# TUSB8041_Connectors_2.net
KiCad netlist of a schematic drawn in Altium Designer
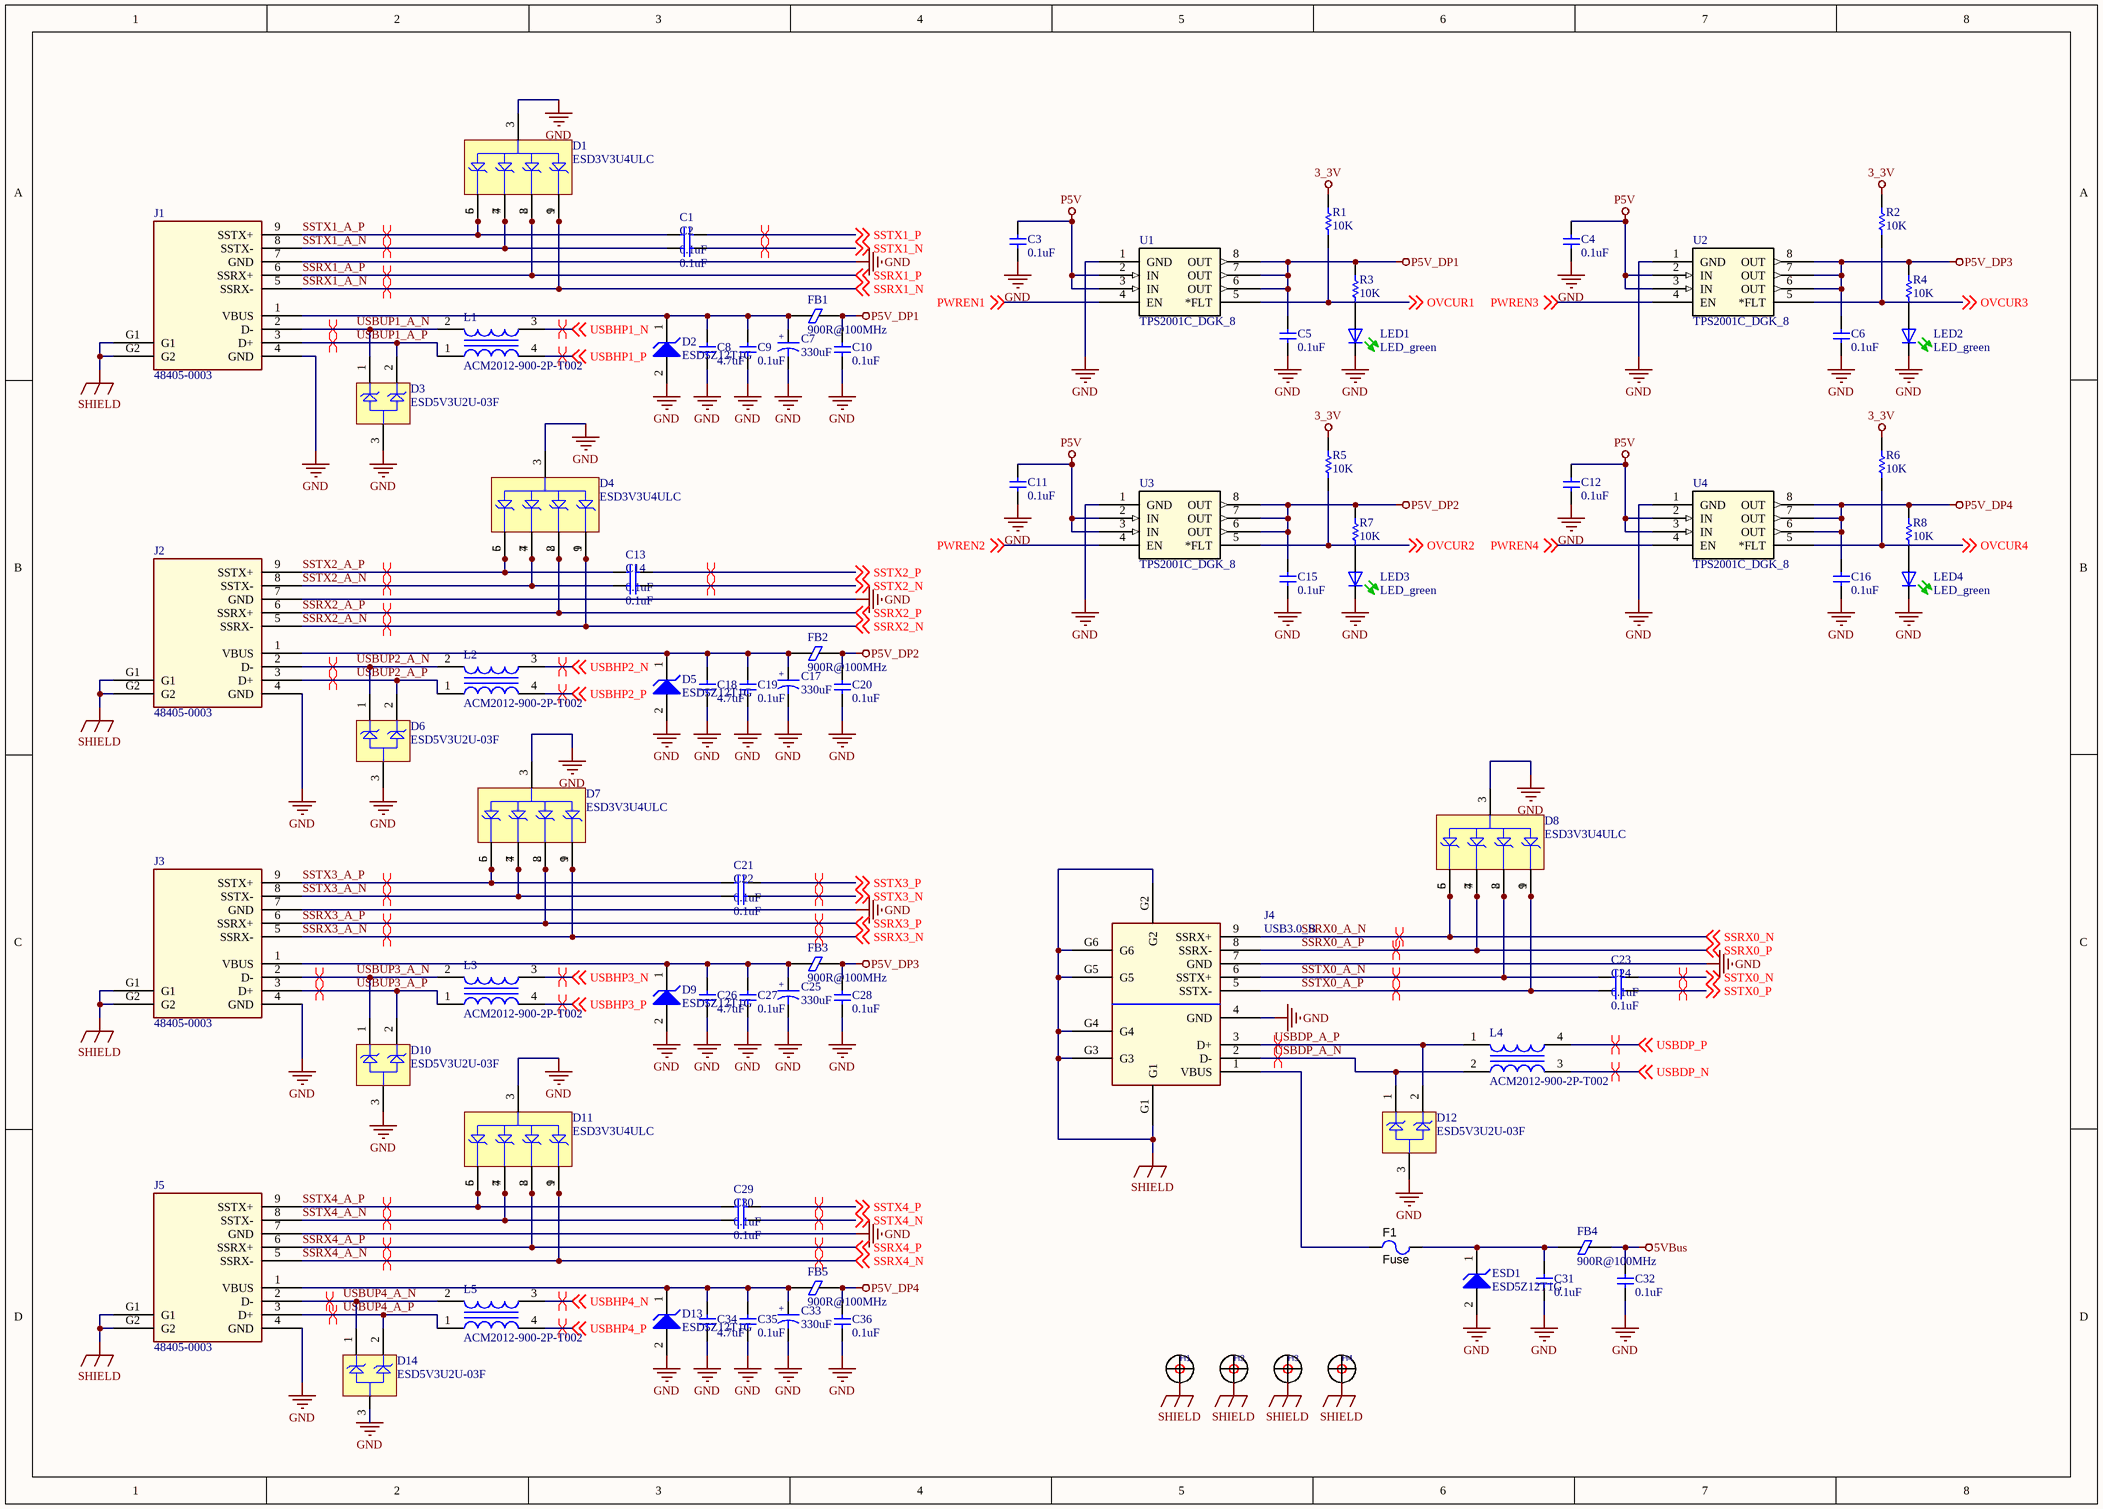
[diagram p0: TUSB8041_Connectors_2.SchDoc]

(export (version "E")
  (design (tool "Eeschema 10.0.6"))
  (components
    (comp (ref "C1")
      (value "0.1uF")
      (footprint "CAP0402")
      (description "Capacitor")
      (fields (field (name "PUBLISHER") "Altium Limited"))
      (libsource (lib "TUSB8041_USB_3.0_Hub") (part "CAP"))
    )
    (comp (ref "C2")
      (value "0.1uF")
      (footprint "CAP0402")
      (description "Capacitor")
      (fields (field (name "PUBLISHER") "Altium Limited"))
      (libsource (lib "TUSB8041_USB_3.0_Hub") (part "CAP"))
    )
    (comp (ref "C3")
      (value "0.1uF")
      (footprint "CAP0603")
      (description "Capacitor")
      (fields (field (name "PUBLISHER") "Altium Limited"))
      (libsource (lib "TUSB8041_USB_3.0_Hub") (part "CAP"))
    )
    (comp (ref "C4")
      (value "0.1uF")
      (footprint "CAP0603")
      (description "Capacitor")
      (fields (field (name "PUBLISHER") "Altium Limited"))
      (libsource (lib "TUSB8041_USB_3.0_Hub") (part "CAP"))
    )
    (comp (ref "C5")
      (value "0.1uF")
      (footprint "CAP0603")
      (description "Capacitor")
      (fields (field (name "PUBLISHER") "Altium Limited"))
      (libsource (lib "TUSB8041_USB_3.0_Hub") (part "CAP"))
    )
    (comp (ref "C6")
      (value "0.1uF")
      (footprint "CAP0603")
      (description "Capacitor")
      (fields (field (name "PUBLISHER") "Altium Limited"))
      (libsource (lib "TUSB8041_USB_3.0_Hub") (part "CAP"))
    )
    (comp (ref "C7")
      (value "330uF")
      (footprint "CAP7343_TANT")
      (libsource (lib "TUSB8041_USB_3.0_Hub") (part "CAP_POL"))
    )
    (comp (ref "C8")
      (value "4.7uF")
      (footprint "CAP0603")
      (description "Capacitor")
      (fields (field (name "PUBLISHER") "Altium Limited"))
      (libsource (lib "TUSB8041_USB_3.0_Hub") (part "CAP"))
    )
    (comp (ref "C9")
      (value "0.1uF")
      (footprint "CAP0603")
      (description "Capacitor")
      (fields (field (name "PUBLISHER") "Altium Limited"))
      (libsource (lib "TUSB8041_USB_3.0_Hub") (part "CAP"))
    )
    (comp (ref "C10")
      (value "0.1uF")
      (footprint "CAP0603")
      (description "Capacitor")
      (fields (field (name "PUBLISHER") "Altium Limited"))
      (libsource (lib "TUSB8041_USB_3.0_Hub") (part "CAP"))
    )
    (comp (ref "C11")
      (value "0.1uF")
      (footprint "CAP0603")
      (description "Capacitor")
      (fields (field (name "PUBLISHER") "Altium Limited"))
      (libsource (lib "TUSB8041_USB_3.0_Hub") (part "CAP"))
    )
    (comp (ref "C12")
      (value "0.1uF")
      (footprint "CAP0603")
      (description "Capacitor")
      (fields (field (name "PUBLISHER") "Altium Limited"))
      (libsource (lib "TUSB8041_USB_3.0_Hub") (part "CAP"))
    )
    (comp (ref "C13")
      (value "0.1uF")
      (footprint "CAP0402")
      (description "Capacitor")
      (fields (field (name "PUBLISHER") "Altium Limited"))
      (libsource (lib "TUSB8041_USB_3.0_Hub") (part "CAP"))
    )
    (comp (ref "C14")
      (value "0.1uF")
      (footprint "CAP0402")
      (description "Capacitor")
      (fields (field (name "PUBLISHER") "Altium Limited"))
      (libsource (lib "TUSB8041_USB_3.0_Hub") (part "CAP"))
    )
    (comp (ref "C15")
      (value "0.1uF")
      (footprint "CAP0603")
      (description "Capacitor")
      (fields (field (name "PUBLISHER") "Altium Limited"))
      (libsource (lib "TUSB8041_USB_3.0_Hub") (part "CAP"))
    )
    (comp (ref "C16")
      (value "0.1uF")
      (footprint "CAP0603")
      (description "Capacitor")
      (fields (field (name "PUBLISHER") "Altium Limited"))
      (libsource (lib "TUSB8041_USB_3.0_Hub") (part "CAP"))
    )
    (comp (ref "C17")
      (value "330uF")
      (footprint "CAP7343_TANT")
      (libsource (lib "TUSB8041_USB_3.0_Hub") (part "CAP_POL"))
    )
    (comp (ref "C18")
      (value "4.7uF")
      (footprint "CAP0603")
      (description "Capacitor")
      (fields (field (name "PUBLISHER") "Altium Limited"))
      (libsource (lib "TUSB8041_USB_3.0_Hub") (part "CAP"))
    )
    (comp (ref "C19")
      (value "0.1uF")
      (footprint "CAP0603")
      (description "Capacitor")
      (fields (field (name "PUBLISHER") "Altium Limited"))
      (libsource (lib "TUSB8041_USB_3.0_Hub") (part "CAP"))
    )
    (comp (ref "C20")
      (value "0.1uF")
      (footprint "CAP0603")
      (description "Capacitor")
      (fields (field (name "PUBLISHER") "Altium Limited"))
      (libsource (lib "TUSB8041_USB_3.0_Hub") (part "CAP"))
    )
    (comp (ref "C21")
      (value "0.1uF")
      (footprint "CAP0402")
      (description "Capacitor")
      (fields (field (name "PUBLISHER") "Altium Limited"))
      (libsource (lib "TUSB8041_USB_3.0_Hub") (part "CAP"))
    )
    (comp (ref "C22")
      (value "0.1uF")
      (footprint "CAP0402")
      (description "Capacitor")
      (fields (field (name "PUBLISHER") "Altium Limited"))
      (libsource (lib "TUSB8041_USB_3.0_Hub") (part "CAP"))
    )
    (comp (ref "C23")
      (value "0.1uF")
      (footprint "CAP0402")
      (description "Capacitor")
      (fields (field (name "PUBLISHER") "Altium Limited"))
      (libsource (lib "TUSB8041_USB_3.0_Hub") (part "CAP"))
    )
    (comp (ref "C24")
      (value "0.1uF")
      (footprint "CAP0402")
      (description "Capacitor")
      (fields (field (name "PUBLISHER") "Altium Limited"))
      (libsource (lib "TUSB8041_USB_3.0_Hub") (part "CAP"))
    )
    (comp (ref "C25")
      (value "330uF")
      (footprint "CAP7343_TANT")
      (libsource (lib "TUSB8041_USB_3.0_Hub") (part "CAP_POL"))
    )
    (comp (ref "C26")
      (value "4.7uF")
      (footprint "CAP0603")
      (description "Capacitor")
      (fields (field (name "PUBLISHER") "Altium Limited"))
      (libsource (lib "TUSB8041_USB_3.0_Hub") (part "CAP"))
    )
    (comp (ref "C27")
      (value "0.1uF")
      (footprint "CAP0603")
      (description "Capacitor")
      (fields (field (name "PUBLISHER") "Altium Limited"))
      (libsource (lib "TUSB8041_USB_3.0_Hub") (part "CAP"))
    )
    (comp (ref "C28")
      (value "0.1uF")
      (footprint "CAP0603")
      (description "Capacitor")
      (fields (field (name "PUBLISHER") "Altium Limited"))
      (libsource (lib "TUSB8041_USB_3.0_Hub") (part "CAP"))
    )
    (comp (ref "C29")
      (value "0.1uF")
      (footprint "CAP0402")
      (description "Capacitor")
      (fields (field (name "PUBLISHER") "Altium Limited"))
      (libsource (lib "TUSB8041_USB_3.0_Hub") (part "CAP"))
    )
    (comp (ref "C30")
      (value "0.1uF")
      (footprint "CAP0402")
      (description "Capacitor")
      (fields (field (name "PUBLISHER") "Altium Limited"))
      (libsource (lib "TUSB8041_USB_3.0_Hub") (part "CAP"))
    )
    (comp (ref "C31")
      (value "0.1uF")
      (footprint "CAP0603")
      (description "Capacitor")
      (fields (field (name "PUBLISHER") "Altium Limited"))
      (libsource (lib "TUSB8041_USB_3.0_Hub") (part "CAP"))
    )
    (comp (ref "C32")
      (value "0.1uF")
      (footprint "CAP0603")
      (description "Capacitor")
      (fields (field (name "PUBLISHER") "Altium Limited"))
      (libsource (lib "TUSB8041_USB_3.0_Hub") (part "CAP"))
    )
    (comp (ref "C33")
      (value "330uF")
      (footprint "CAP7343_TANT")
      (libsource (lib "TUSB8041_USB_3.0_Hub") (part "CAP_POL"))
    )
    (comp (ref "C34")
      (value "4.7uF")
      (footprint "CAP0603")
      (description "Capacitor")
      (fields (field (name "PUBLISHER") "Altium Limited"))
      (libsource (lib "TUSB8041_USB_3.0_Hub") (part "CAP"))
    )
    (comp (ref "C35")
      (value "0.1uF")
      (footprint "CAP0603")
      (description "Capacitor")
      (fields (field (name "PUBLISHER") "Altium Limited"))
      (libsource (lib "TUSB8041_USB_3.0_Hub") (part "CAP"))
    )
    (comp (ref "C36")
      (value "0.1uF")
      (footprint "CAP0603")
      (description "Capacitor")
      (fields (field (name "PUBLISHER") "Altium Limited"))
      (libsource (lib "TUSB8041_USB_3.0_Hub") (part "CAP"))
    )
    (comp (ref "D1")
      (value "ESD3V3U4ULC")
      (footprint "PG-TSLP-9-1")
      (description "Ultra-Low Capacitance ESD / Transient Protection Array, -40 to 125 degC, PG-TSLP-9-1, Reel, Green")
      (fields (field (name "MANUFACTURER") "Infineon"))
      (libsource (lib "小车") (part "ESD3V3U4ULC"))
    )
    (comp (ref "D2")
      (value "ESD5Z12T1G")
      (footprint "ONSC-SOD-523-2-502-01_V")
      (fields (field (name "MANUFACTURER") "On Semiconductor"))
      (libsource (lib "Altium Content Vault") (part "ONSC-K1A2-2"))
    )
    (comp (ref "D3")
      (value "ESD5V3U2U-03F")
      (footprint "INF-PG-TSFP-3-1_V")
      (description "Ultra-Low Capacitance ESD Diode Array, -40 to 125 degC, PG-TSFP-3-1, Reel, Green")
      (fields (field (name "MANUFACTURER") "Infineon"))
      (libsource (lib "Altium Content Vault") (part "INF-D_K1K2A3-3-A"))
    )
    (comp (ref "D4")
      (value "ESD3V3U4ULC")
      (footprint "PG-TSLP-9-1")
      (description "Ultra-Low Capacitance ESD / Transient Protection Array, -40 to 125 degC, PG-TSLP-9-1, Reel, Green")
      (fields (field (name "MANUFACTURER") "Infineon"))
      (libsource (lib "小车") (part "ESD3V3U4ULC"))
    )
    (comp (ref "D5")
      (value "ESD5Z12T1G")
      (footprint "ONSC-SOD-523-2-502-01_V")
      (fields (field (name "MANUFACTURER") "On Semiconductor"))
      (libsource (lib "Altium Content Vault") (part "ONSC-K1A2-2"))
    )
    (comp (ref "D6")
      (value "ESD5V3U2U-03F")
      (footprint "INF-PG-TSFP-3-1_V")
      (description "Ultra-Low Capacitance ESD Diode Array, -40 to 125 degC, PG-TSFP-3-1, Reel, Green")
      (fields (field (name "MANUFACTURER") "Infineon"))
      (libsource (lib "Altium Content Vault") (part "INF-D_K1K2A3-3-A"))
    )
    (comp (ref "D7")
      (value "ESD3V3U4ULC")
      (footprint "PG-TSLP-9-1")
      (description "Ultra-Low Capacitance ESD / Transient Protection Array, -40 to 125 degC, PG-TSLP-9-1, Reel, Green")
      (fields (field (name "MANUFACTURER") "Infineon"))
      (libsource (lib "小车") (part "ESD3V3U4ULC"))
    )
    (comp (ref "D8")
      (value "ESD3V3U4ULC")
      (footprint "PG-TSLP-9-1")
      (description "Ultra-Low Capacitance ESD / Transient Protection Array, -40 to 125 degC, PG-TSLP-9-1, Reel, Green")
      (fields (field (name "MANUFACTURER") "Infineon"))
      (libsource (lib "小车") (part "ESD3V3U4ULC"))
    )
    (comp (ref "D9")
      (value "ESD5Z12T1G")
      (footprint "ONSC-SOD-523-2-502-01_V")
      (fields (field (name "MANUFACTURER") "On Semiconductor"))
      (libsource (lib "Altium Content Vault") (part "ONSC-K1A2-2"))
    )
    (comp (ref "D10")
      (value "ESD5V3U2U-03F")
      (footprint "INF-PG-TSFP-3-1_V")
      (description "Ultra-Low Capacitance ESD Diode Array, -40 to 125 degC, PG-TSFP-3-1, Reel, Green")
      (fields (field (name "MANUFACTURER") "Infineon"))
      (libsource (lib "Altium Content Vault") (part "INF-D_K1K2A3-3-A"))
    )
    (comp (ref "D11")
      (value "ESD3V3U4ULC")
      (footprint "PG-TSLP-9-1")
      (description "Ultra-Low Capacitance ESD / Transient Protection Array, -40 to 125 degC, PG-TSLP-9-1, Reel, Green")
      (fields (field (name "MANUFACTURER") "Infineon"))
      (libsource (lib "小车") (part "ESD3V3U4ULC"))
    )
    (comp (ref "D12")
      (value "ESD5V3U2U-03F")
      (footprint "INF-PG-TSFP-3-1_V")
      (description "Ultra-Low Capacitance ESD Diode Array, -40 to 125 degC, PG-TSFP-3-1, Reel, Green")
      (fields (field (name "MANUFACTURER") "Infineon"))
      (libsource (lib "Altium Content Vault") (part "INF-D_K1K2A3-3-A"))
    )
    (comp (ref "D13")
      (value "ESD5Z12T1G")
      (footprint "ONSC-SOD-523-2-502-01_V")
      (fields (field (name "MANUFACTURER") "On Semiconductor"))
      (libsource (lib "Altium Content Vault") (part "ONSC-K1A2-2"))
    )
    (comp (ref "D14")
      (value "ESD5V3U2U-03F")
      (footprint "INF-PG-TSFP-3-1_V")
      (description "Ultra-Low Capacitance ESD Diode Array, -40 to 125 degC, PG-TSFP-3-1, Reel, Green")
      (fields (field (name "MANUFACTURER") "Infineon"))
      (libsource (lib "Altium Content Vault") (part "INF-D_K1K2A3-3-A"))
    )
    (comp (ref "ESD1")
      (value "ESD5Z12T1G")
      (footprint "ONSC-SOD-523-2-502-01_V")
      (fields (field (name "MANUFACTURER") "On Semiconductor"))
      (libsource (lib "Altium Content Vault") (part "ONSC-K1A2-2"))
    )
    (comp (ref "F1")
      (value "Fuse")
      (footprint "FUSE1206")
      (fields
        (field (name "PARTNUMBER") "NANOSMDC020F-2")
        (field (name "MANUFACTURER") "TE Connectivity")
        (field (name "PUBLISHER") "Texas Instruments")
        (field (name "SYMBOLCREATOR") "a0412235")
      )
      (libsource (lib "TUSB8041_USB_3.0_Hub") (part "Fuse"))
    )
    (comp (ref "FB1")
      (value "900R@100MHz")
      (footprint "L0805")
      (libsource (lib "TUSB8041_USB_3.0_Hub") (part "Ferrite Bead"))
    )
    (comp (ref "FB2")
      (value "900R@100MHz")
      (footprint "L0805")
      (libsource (lib "TUSB8041_USB_3.0_Hub") (part "Ferrite Bead"))
    )
    (comp (ref "FB3")
      (value "900R@100MHz")
      (footprint "L0805")
      (libsource (lib "TUSB8041_USB_3.0_Hub") (part "Ferrite Bead"))
    )
    (comp (ref "FB4")
      (value "900R@100MHz")
      (footprint "L0805")
      (libsource (lib "TUSB8041_USB_3.0_Hub") (part "Ferrite Bead"))
    )
    (comp (ref "FB5")
      (value "900R@100MHz")
      (footprint "L0805")
      (libsource (lib "TUSB8041_USB_3.0_Hub") (part "Ferrite Bead"))
    )
    (comp (ref "H1")
      (value "HOLE")
      (footprint "HOLE_Φ3_1_2D")
      (libsource (lib "TUSB8041_USB_3.0_Hub") (part "HOLE"))
    )
    (comp (ref "H2")
      (value "HOLE")
      (footprint "HOLE_Φ3_1_2D")
      (libsource (lib "TUSB8041_USB_3.0_Hub") (part "HOLE"))
    )
    (comp (ref "H3")
      (value "HOLE")
      (footprint "HOLE_Φ3_1_2D")
      (libsource (lib "TUSB8041_USB_3.0_Hub") (part "HOLE"))
    )
    (comp (ref "H4")
      (value "HOLE")
      (footprint "HOLE_Φ3_1_2D")
      (libsource (lib "TUSB8041_USB_3.0_Hub") (part "HOLE"))
    )
    (comp (ref "J1")
      (value "48405-0003")
      (footprint "CN_USB30_A")
      (libsource (lib "TUSB8041_USB_3.0_Hub") (part "USB-UEA11123-4HK1-4H"))
    )
    (comp (ref "J2")
      (value "48405-0003")
      (footprint "CN_USB30_A")
      (libsource (lib "TUSB8041_USB_3.0_Hub") (part "USB-UEA11123-4HK1-4H"))
    )
    (comp (ref "J3")
      (value "48405-0003")
      (footprint "CN_USB30_A")
      (libsource (lib "TUSB8041_USB_3.0_Hub") (part "USB-UEA11123-4HK1-4H"))
    )
    (comp (ref "J4")
      (value "USB3.0_B")
      (footprint "ASS_4224_CO")
      (libsource (lib "TUSB8041_USB_3.0_Hub") (part "USB3.0_B"))
    )
    (comp (ref "J5")
      (value "48405-0003")
      (footprint "CN_USB30_A")
      (libsource (lib "TUSB8041_USB_3.0_Hub") (part "USB-UEA11123-4HK1-4H"))
    )
    (comp (ref "L1")
      (value "ACM2012-900-2P-T002")
      (footprint "TDK-ACM2012_V")
      (description "Common Mode Filter, 90 Ohm, 50 V, -40 to 85 degC, 4-Pin SMD, RoHS, Tape and Reel")
      (fields (field (name "PART NO") "ACM2012-900-2P-T") (field (name "MANUFACTURER") "TDKCorporation"))
      (libsource (lib "Altium Content Vault") (part "IND-CHOKE-4_C"))
    )
    (comp (ref "L2")
      (value "ACM2012-900-2P-T002")
      (footprint "TDK-ACM2012_V")
      (description "Common Mode Filter, 90 Ohm, 50 V, -40 to 85 degC, 4-Pin SMD, RoHS, Tape and Reel")
      (fields (field (name "PART NO") "ACM2012-900-2P-T") (field (name "MANUFACTURER") "TDKCorporation"))
      (libsource (lib "Altium Content Vault") (part "IND-CHOKE-4_C"))
    )
    (comp (ref "L3")
      (value "ACM2012-900-2P-T002")
      (footprint "TDK-ACM2012_V")
      (description "Common Mode Filter, 90 Ohm, 50 V, -40 to 85 degC, 4-Pin SMD, RoHS, Tape and Reel")
      (fields (field (name "PART NO") "ACM2012-900-2P-T") (field (name "MANUFACTURER") "TDKCorporation"))
      (libsource (lib "Altium Content Vault") (part "IND-CHOKE-4_C"))
    )
    (comp (ref "L4")
      (value "ACM2012-900-2P-T002")
      (footprint "TDK-ACM2012_V")
      (description "Common Mode Filter, 90 Ohm, 50 V, -40 to 85 degC, 4-Pin SMD, RoHS, Tape and Reel")
      (fields (field (name "PART NO") "ACM2012-900-2P-T") (field (name "MANUFACTURER") "TDKCorporation"))
      (libsource (lib "") (part "IND-CHOKE-4_C_1"))
    )
    (comp (ref "L5")
      (value "ACM2012-900-2P-T002")
      (footprint "TDK-ACM2012_V")
      (description "Common Mode Filter, 90 Ohm, 50 V, -40 to 85 degC, 4-Pin SMD, RoHS, Tape and Reel")
      (fields (field (name "PART NO") "ACM2012-900-2P-T") (field (name "MANUFACTURER") "TDKCorporation"))
      (libsource (lib "Altium Content Vault") (part "IND-CHOKE-4_C"))
    )
    (comp (ref "LED1")
      (value "LED_green")
      (footprint "LED-0603-GREEN")
      (libsource (lib "TUSB8041_USB_3.0_Hub") (part "LED_green"))
    )
    (comp (ref "LED2")
      (value "LED_green")
      (footprint "LED-0603-GREEN")
      (libsource (lib "TUSB8041_USB_3.0_Hub") (part "LED_green"))
    )
    (comp (ref "LED3")
      (value "LED_green")
      (footprint "LED-0603-GREEN")
      (libsource (lib "TUSB8041_USB_3.0_Hub") (part "LED_green"))
    )
    (comp (ref "LED4")
      (value "LED_green")
      (footprint "LED-0603-GREEN")
      (libsource (lib "TUSB8041_USB_3.0_Hub") (part "LED_green"))
    )
    (comp (ref "R1")
      (value "10K")
      (footprint "RES0603")
      (description "Resistor")
      (fields (field (name "PUBLISHER") "Altium Limited"))
      (libsource (lib "TUSB8041_USB_3.0_Hub") (part "RES"))
    )
    (comp (ref "R2")
      (value "10K")
      (footprint "RES0603")
      (description "Resistor")
      (fields (field (name "PUBLISHER") "Altium Limited"))
      (libsource (lib "TUSB8041_USB_3.0_Hub") (part "RES"))
    )
    (comp (ref "R3")
      (value "10K")
      (footprint "RES0603")
      (description "Resistor")
      (fields (field (name "PUBLISHER") "Altium Limited"))
      (libsource (lib "TUSB8041_USB_3.0_Hub") (part "RES"))
    )
    (comp (ref "R4")
      (value "10K")
      (footprint "RES0603")
      (description "Resistor")
      (fields (field (name "PUBLISHER") "Altium Limited"))
      (libsource (lib "TUSB8041_USB_3.0_Hub") (part "RES"))
    )
    (comp (ref "R5")
      (value "10K")
      (footprint "RES0603")
      (description "Resistor")
      (fields (field (name "PUBLISHER") "Altium Limited"))
      (libsource (lib "TUSB8041_USB_3.0_Hub") (part "RES"))
    )
    (comp (ref "R6")
      (value "10K")
      (footprint "RES0603")
      (description "Resistor")
      (fields (field (name "PUBLISHER") "Altium Limited"))
      (libsource (lib "TUSB8041_USB_3.0_Hub") (part "RES"))
    )
    (comp (ref "R7")
      (value "10K")
      (footprint "RES0603")
      (description "Resistor")
      (fields (field (name "PUBLISHER") "Altium Limited"))
      (libsource (lib "TUSB8041_USB_3.0_Hub") (part "RES"))
    )
    (comp (ref "R8")
      (value "10K")
      (footprint "RES0603")
      (description "Resistor")
      (fields (field (name "PUBLISHER") "Altium Limited"))
      (libsource (lib "TUSB8041_USB_3.0_Hub") (part "RES"))
    )
    (comp (ref "U1")
      (value "TPS2001C_DGK_8")
      (footprint "VSSOP8")
      (description "2A_MOS_PSW")
      (fields
        (field (name "MANUFACTURER_PART_NUMBER") "tps2001c_dgk_8")
        (field (name "GENERIC_PART_NUMBER") "TPS2001C")
      )
      (libsource (lib "TUSB8041_USB_3.0_Hub") (part "TPS2001C_DGK_8"))
    )
    (comp (ref "U2")
      (value "TPS2001C_DGK_8")
      (footprint "VSSOP8")
      (description "2A_MOS_PSW")
      (fields
        (field (name "MANUFACTURER_PART_NUMBER") "tps2001c_dgk_8")
        (field (name "GENERIC_PART_NUMBER") "TPS2001C")
      )
      (libsource (lib "TUSB8041_USB_3.0_Hub") (part "TPS2001C_DGK_8"))
    )
    (comp (ref "U3")
      (value "TPS2001C_DGK_8")
      (footprint "VSSOP8")
      (description "2A_MOS_PSW")
      (fields
        (field (name "MANUFACTURER_PART_NUMBER") "tps2001c_dgk_8")
        (field (name "GENERIC_PART_NUMBER") "TPS2001C")
      )
      (libsource (lib "TUSB8041_USB_3.0_Hub") (part "TPS2001C_DGK_8"))
    )
    (comp (ref "U4")
      (value "TPS2001C_DGK_8")
      (footprint "VSSOP8")
      (description "2A_MOS_PSW")
      (fields
        (field (name "MANUFACTURER_PART_NUMBER") "tps2001c_dgk_8")
        (field (name "GENERIC_PART_NUMBER") "TPS2001C")
      )
      (libsource (lib "TUSB8041_USB_3.0_Hub") (part "TPS2001C_DGK_8"))
    )
  )
  (nets
    (net (code "1") (name "/SSTX0_A_N") (class "Default")
      (node (ref "C23") (pin "2") (pinfunction "2_2") (pintype "passive"))
      (node (ref "D8") (pin "2") (pinfunction "K2_2") (pintype "passive"))
      (node (ref "D8") (pin "8") (pinfunction "K8_8") (pintype "passive"))
      (node (ref "J4") (pin "6") (pinfunction "SSTX+_6") (pintype "passive"))
    )
    (net (code "2") (name "/SSTX0_A_P") (class "Default")
      (node (ref "C24") (pin "2") (pinfunction "2_2") (pintype "passive"))
      (node (ref "D8") (pin "1") (pinfunction "K1_1") (pintype "passive"))
      (node (ref "D8") (pin "9") (pinfunction "K9_9") (pintype "passive"))
      (node (ref "J4") (pin "5") (pinfunction "SSTX-_5") (pintype "passive"))
    )
    (net (code "3") (name "/SSTX1_A_N") (class "Default")
      (node (ref "C2") (pin "2") (pinfunction "2_2") (pintype "passive"))
      (node (ref "D1") (pin "4") (pinfunction "K4_4") (pintype "passive"))
      (node (ref "D1") (pin "7") (pinfunction "K7_7") (pintype "passive"))
      (node (ref "J1") (pin "8") (pinfunction "SSTX-_8") (pintype "passive"))
    )
    (net (code "4") (name "/SSTX1_A_P") (class "Default")
      (node (ref "C1") (pin "2") (pinfunction "2_2") (pintype "passive"))
      (node (ref "D1") (pin "5") (pinfunction "K5_5") (pintype "passive"))
      (node (ref "D1") (pin "6") (pinfunction "K6_6") (pintype "passive"))
      (node (ref "J1") (pin "9") (pinfunction "SSTX+_9") (pintype "passive"))
    )
    (net (code "5") (name "/SSTX2_A_N") (class "Default")
      (node (ref "C14") (pin "2") (pinfunction "2_2") (pintype "passive"))
      (node (ref "D4") (pin "4") (pinfunction "K4_4") (pintype "passive"))
      (node (ref "D4") (pin "7") (pinfunction "K7_7") (pintype "passive"))
      (node (ref "J2") (pin "8") (pinfunction "SSTX-_8") (pintype "passive"))
    )
    (net (code "6") (name "/SSTX2_A_P") (class "Default")
      (node (ref "C13") (pin "2") (pinfunction "2_2") (pintype "passive"))
      (node (ref "D4") (pin "5") (pinfunction "K5_5") (pintype "passive"))
      (node (ref "D4") (pin "6") (pinfunction "K6_6") (pintype "passive"))
      (node (ref "J2") (pin "9") (pinfunction "SSTX+_9") (pintype "passive"))
    )
    (net (code "7") (name "/SSTX3_A_N") (class "Default")
      (node (ref "C22") (pin "2") (pinfunction "2_2") (pintype "passive"))
      (node (ref "D7") (pin "4") (pinfunction "K4_4") (pintype "passive"))
      (node (ref "D7") (pin "7") (pinfunction "K7_7") (pintype "passive"))
      (node (ref "J3") (pin "8") (pinfunction "SSTX-_8") (pintype "passive"))
    )
    (net (code "8") (name "/SSTX3_A_P") (class "Default")
      (node (ref "C21") (pin "2") (pinfunction "2_2") (pintype "passive"))
      (node (ref "D7") (pin "5") (pinfunction "K5_5") (pintype "passive"))
      (node (ref "D7") (pin "6") (pinfunction "K6_6") (pintype "passive"))
      (node (ref "J3") (pin "9") (pinfunction "SSTX+_9") (pintype "passive"))
    )
    (net (code "9") (name "/SSTX4_A_N") (class "Default")
      (node (ref "C30") (pin "2") (pinfunction "2_2") (pintype "passive"))
      (node (ref "D11") (pin "4") (pinfunction "K4_4") (pintype "passive"))
      (node (ref "D11") (pin "7") (pinfunction "K7_7") (pintype "passive"))
      (node (ref "J5") (pin "8") (pinfunction "SSTX-_8") (pintype "passive"))
    )
    (net (code "10") (name "/SSTX4_A_P") (class "Default")
      (node (ref "C29") (pin "2") (pinfunction "2_2") (pintype "passive"))
      (node (ref "D11") (pin "5") (pinfunction "K5_5") (pintype "passive"))
      (node (ref "D11") (pin "6") (pinfunction "K6_6") (pintype "passive"))
      (node (ref "J5") (pin "9") (pinfunction "SSTX+_9") (pintype "passive"))
    )
    (net (code "11") (name "/USBDP_A_N") (class "Default")
      (node (ref "D12") (pin "1") (pinfunction "K1_1") (pintype "passive"))
      (node (ref "J4") (pin "2") (pinfunction "D-_2") (pintype "passive"))
      (node (ref "L4") (pin "2") (pinfunction "2_2") (pintype "passive"))
    )
    (net (code "12") (name "/USBDP_A_P") (class "Default")
      (node (ref "D12") (pin "2") (pinfunction "K2_2") (pintype "passive"))
      (node (ref "J4") (pin "3") (pinfunction "D+_3") (pintype "passive"))
      (node (ref "L4") (pin "1") (pinfunction "1_1") (pintype "passive"))
    )
    (net (code "13") (name "/USBUP1_A_N") (class "Default")
      (node (ref "D3") (pin "1") (pinfunction "K1_1") (pintype "passive"))
      (node (ref "J1") (pin "2") (pinfunction "D-_2") (pintype "passive"))
      (node (ref "L1") (pin "2") (pinfunction "2_2") (pintype "passive"))
    )
    (net (code "14") (name "/USBUP1_A_P") (class "Default")
      (node (ref "D3") (pin "2") (pinfunction "K2_2") (pintype "passive"))
      (node (ref "J1") (pin "3") (pinfunction "D+_3") (pintype "passive"))
      (node (ref "L1") (pin "1") (pinfunction "1_1") (pintype "passive"))
    )
    (net (code "15") (name "/USBUP2_A_N") (class "Default")
      (node (ref "D6") (pin "1") (pinfunction "K1_1") (pintype "passive"))
      (node (ref "J2") (pin "2") (pinfunction "D-_2") (pintype "passive"))
      (node (ref "L2") (pin "2") (pinfunction "2_2") (pintype "passive"))
    )
    (net (code "16") (name "/USBUP2_A_P") (class "Default")
      (node (ref "D6") (pin "2") (pinfunction "K2_2") (pintype "passive"))
      (node (ref "J2") (pin "3") (pinfunction "D+_3") (pintype "passive"))
      (node (ref "L2") (pin "1") (pinfunction "1_1") (pintype "passive"))
    )
    (net (code "17") (name "/USBUP3_A_N") (class "Default")
      (node (ref "D10") (pin "1") (pinfunction "K1_1") (pintype "passive"))
      (node (ref "J3") (pin "2") (pinfunction "D-_2") (pintype "passive"))
      (node (ref "L3") (pin "2") (pinfunction "2_2") (pintype "passive"))
    )
    (net (code "18") (name "/USBUP3_A_P") (class "Default")
      (node (ref "D10") (pin "2") (pinfunction "K2_2") (pintype "passive"))
      (node (ref "J3") (pin "3") (pinfunction "D+_3") (pintype "passive"))
      (node (ref "L3") (pin "1") (pinfunction "1_1") (pintype "passive"))
    )
    (net (code "19") (name "/USBUP4_A_N") (class "Default")
      (node (ref "D14") (pin "1") (pinfunction "K1_1") (pintype "passive"))
      (node (ref "J5") (pin "2") (pinfunction "D-_2") (pintype "passive"))
      (node (ref "L5") (pin "2") (pinfunction "2_2") (pintype "passive"))
    )
    (net (code "20") (name "/USBUP4_A_P") (class "Default")
      (node (ref "D14") (pin "2") (pinfunction "K2_2") (pintype "passive"))
      (node (ref "J5") (pin "3") (pinfunction "D+_3") (pintype "passive"))
      (node (ref "L5") (pin "1") (pinfunction "1_1") (pintype "passive"))
    )
    (net (code "21") (name "3_3V") (class "Default")
      (node (ref "R1") (pin "1") (pinfunction "1_1") (pintype "passive"))
      (node (ref "R2") (pin "1") (pinfunction "1_1") (pintype "passive"))
      (node (ref "R5") (pin "1") (pinfunction "1_1") (pintype "passive"))
      (node (ref "R6") (pin "1") (pinfunction "1_1") (pintype "passive"))
    )
    (net (code "22") (name "5VBus") (class "Default")
      (node (ref "C32") (pin "2") (pinfunction "2_2") (pintype "passive"))
      (node (ref "FB4") (pin "2") (pintype "passive"))
    )
    (net (code "23") (name "GND") (class "Default")
      (node (ref "C10") (pin "1") (pinfunction "1_1") (pintype "passive"))
      (node (ref "C11") (pin "1") (pinfunction "1_1") (pintype "passive"))
      (node (ref "C12") (pin "1") (pinfunction "1_1") (pintype "passive"))
      (node (ref "C15") (pin "1") (pinfunction "1_1") (pintype "passive"))
      (node (ref "C16") (pin "1") (pinfunction "1_1") (pintype "passive"))
      (node (ref "C17") (pin "2") (pinfunction "2_2") (pintype "passive"))
      (node (ref "C18") (pin "1") (pinfunction "1_1") (pintype "passive"))
      (node (ref "C19") (pin "1") (pinfunction "1_1") (pintype "passive"))
      (node (ref "C20") (pin "1") (pinfunction "1_1") (pintype "passive"))
      (node (ref "C25") (pin "2") (pinfunction "2_2") (pintype "passive"))
      (node (ref "C26") (pin "1") (pinfunction "1_1") (pintype "passive"))
      (node (ref "C27") (pin "1") (pinfunction "1_1") (pintype "passive"))
      (node (ref "C28") (pin "1") (pinfunction "1_1") (pintype "passive"))
      (node (ref "C3") (pin "1") (pinfunction "1_1") (pintype "passive"))
      (node (ref "C31") (pin "1") (pinfunction "1_1") (pintype "passive"))
      (node (ref "C32") (pin "1") (pinfunction "1_1") (pintype "passive"))
      (node (ref "C33") (pin "2") (pinfunction "2_2") (pintype "passive"))
      (node (ref "C34") (pin "1") (pinfunction "1_1") (pintype "passive"))
      (node (ref "C35") (pin "1") (pinfunction "1_1") (pintype "passive"))
      (node (ref "C36") (pin "1") (pinfunction "1_1") (pintype "passive"))
      (node (ref "C4") (pin "1") (pinfunction "1_1") (pintype "passive"))
      (node (ref "C5") (pin "1") (pinfunction "1_1") (pintype "passive"))
      (node (ref "C6") (pin "1") (pinfunction "1_1") (pintype "passive"))
      (node (ref "C7") (pin "2") (pinfunction "2_2") (pintype "passive"))
      (node (ref "C8") (pin "1") (pinfunction "1_1") (pintype "passive"))
      (node (ref "C9") (pin "1") (pinfunction "1_1") (pintype "passive"))
      (node (ref "D1") (pin "3") (pinfunction "A_3") (pintype "passive"))
      (node (ref "D10") (pin "3") (pinfunction "A_3") (pintype "passive"))
      (node (ref "D11") (pin "3") (pinfunction "A_3") (pintype "passive"))
      (node (ref "D12") (pin "3") (pinfunction "A_3") (pintype "passive"))
      (node (ref "D13") (pin "2") (pinfunction "A_2") (pintype "passive"))
      (node (ref "D14") (pin "3") (pinfunction "A_3") (pintype "passive"))
      (node (ref "D2") (pin "2") (pinfunction "A_2") (pintype "passive"))
      (node (ref "D3") (pin "3") (pinfunction "A_3") (pintype "passive"))
      (node (ref "D4") (pin "3") (pinfunction "A_3") (pintype "passive"))
      (node (ref "D5") (pin "2") (pinfunction "A_2") (pintype "passive"))
      (node (ref "D6") (pin "3") (pinfunction "A_3") (pintype "passive"))
      (node (ref "D7") (pin "3") (pinfunction "A_3") (pintype "passive"))
      (node (ref "D8") (pin "3") (pinfunction "A_3") (pintype "passive"))
      (node (ref "D9") (pin "2") (pinfunction "A_2") (pintype "passive"))
      (node (ref "ESD1") (pin "2") (pinfunction "A_2") (pintype "passive"))
      (node (ref "J1") (pin "4") (pinfunction "GND_4") (pintype "power_in"))
      (node (ref "J1") (pin "7") (pinfunction "GND_7") (pintype "power_in"))
      (node (ref "J2") (pin "4") (pinfunction "GND_4") (pintype "power_in"))
      (node (ref "J2") (pin "7") (pinfunction "GND_7") (pintype "power_in"))
      (node (ref "J3") (pin "4") (pinfunction "GND_4") (pintype "power_in"))
      (node (ref "J3") (pin "7") (pinfunction "GND_7") (pintype "power_in"))
      (node (ref "J4") (pin "4") (pinfunction "GND_4") (pintype "power_in"))
      (node (ref "J4") (pin "7") (pinfunction "GND_7") (pintype "power_in"))
      (node (ref "J5") (pin "4") (pinfunction "GND_4") (pintype "power_in"))
      (node (ref "J5") (pin "7") (pinfunction "GND_7") (pintype "power_in"))
      (node (ref "LED1") (pin "K") (pinfunction "C_K") (pintype "power_in"))
      (node (ref "LED2") (pin "K") (pinfunction "C_K") (pintype "power_in"))
      (node (ref "LED3") (pin "K") (pinfunction "C_K") (pintype "power_in"))
      (node (ref "LED4") (pin "K") (pinfunction "C_K") (pintype "power_in"))
      (node (ref "U1") (pin "1") (pinfunction "GND_1") (pintype "power_in"))
      (node (ref "U2") (pin "1") (pinfunction "GND_1") (pintype "power_in"))
      (node (ref "U3") (pin "1") (pinfunction "GND_1") (pintype "power_in"))
      (node (ref "U4") (pin "1") (pinfunction "GND_1") (pintype "power_in"))
    )
    (net (code "24") (name "Net-(D2-K)") (class "Default")
      (node (ref "C7") (pin "1") (pinfunction "1_1") (pintype "passive"))
      (node (ref "C8") (pin "2") (pinfunction "2_2") (pintype "passive"))
      (node (ref "C9") (pin "2") (pinfunction "2_2") (pintype "passive"))
      (node (ref "D2") (pin "1") (pinfunction "K_1") (pintype "passive"))
      (node (ref "FB1") (pin "1") (pintype "passive"))
      (node (ref "J1") (pin "1") (pinfunction "VBUS_1") (pintype "passive"))
    )
    (net (code "25") (name "Net-(D5-K)") (class "Default")
      (node (ref "C17") (pin "1") (pinfunction "1_1") (pintype "passive"))
      (node (ref "C18") (pin "2") (pinfunction "2_2") (pintype "passive"))
      (node (ref "C19") (pin "2") (pinfunction "2_2") (pintype "passive"))
      (node (ref "D5") (pin "1") (pinfunction "K_1") (pintype "passive"))
      (node (ref "FB2") (pin "1") (pintype "passive"))
      (node (ref "J2") (pin "1") (pinfunction "VBUS_1") (pintype "passive"))
    )
    (net (code "26") (name "Net-(D9-K)") (class "Default")
      (node (ref "C25") (pin "1") (pinfunction "1_1") (pintype "passive"))
      (node (ref "C26") (pin "2") (pinfunction "2_2") (pintype "passive"))
      (node (ref "C27") (pin "2") (pinfunction "2_2") (pintype "passive"))
      (node (ref "D9") (pin "1") (pinfunction "K_1") (pintype "passive"))
      (node (ref "FB3") (pin "1") (pintype "passive"))
      (node (ref "J3") (pin "1") (pinfunction "VBUS_1") (pintype "passive"))
    )
    (net (code "27") (name "Net-(D13-K)") (class "Default")
      (node (ref "C33") (pin "1") (pinfunction "1_1") (pintype "passive"))
      (node (ref "C34") (pin "2") (pinfunction "2_2") (pintype "passive"))
      (node (ref "C35") (pin "2") (pinfunction "2_2") (pintype "passive"))
      (node (ref "D13") (pin "1") (pinfunction "K_1") (pintype "passive"))
      (node (ref "FB5") (pin "1") (pintype "passive"))
      (node (ref "J5") (pin "1") (pinfunction "VBUS_1") (pintype "passive"))
    )
    (net (code "28") (name "Net-(ESD1-K)") (class "Default")
      (node (ref "C31") (pin "2") (pinfunction "2_2") (pintype "passive"))
      (node (ref "ESD1") (pin "1") (pinfunction "K_1") (pintype "passive"))
      (node (ref "F1") (pin "1") (pinfunction "1_1") (pintype "passive"))
      (node (ref "FB4") (pin "1") (pintype "passive"))
    )
    (net (code "29") (name "Net-(J4-VBUS)") (class "Default")
      (node (ref "F1") (pin "2") (pinfunction "2_2") (pintype "passive"))
      (node (ref "J4") (pin "1") (pinfunction "VBUS_1") (pintype "passive"))
    )
    (net (code "30") (name "Net-(LED1-PadA)") (class "Default")
      (node (ref "LED1") (pin "A") (pinfunction "A_A") (pintype "power_in"))
      (node (ref "R3") (pin "2") (pinfunction "2_2") (pintype "passive"))
    )
    (net (code "31") (name "Net-(LED2-PadA)") (class "Default")
      (node (ref "LED2") (pin "A") (pinfunction "A_A") (pintype "power_in"))
      (node (ref "R4") (pin "2") (pinfunction "2_2") (pintype "passive"))
    )
    (net (code "32") (name "Net-(LED3-PadA)") (class "Default")
      (node (ref "LED3") (pin "A") (pinfunction "A_A") (pintype "power_in"))
      (node (ref "R7") (pin "2") (pinfunction "2_2") (pintype "passive"))
    )
    (net (code "33") (name "Net-(LED4-PadA)") (class "Default")
      (node (ref "LED4") (pin "A") (pinfunction "A_A") (pintype "power_in"))
      (node (ref "R8") (pin "2") (pinfunction "2_2") (pintype "passive"))
    )
    (net (code "34") (name "OVCUR1") (class "Default")
      (node (ref "R1") (pin "2") (pinfunction "2_2") (pintype "passive"))
      (node (ref "U1") (pin "5") (pinfunction "*FLT_5") (pintype "passive"))
    )
    (net (code "35") (name "OVCUR2") (class "Default")
      (node (ref "R5") (pin "2") (pinfunction "2_2") (pintype "passive"))
      (node (ref "U3") (pin "5") (pinfunction "*FLT_5") (pintype "passive"))
    )
    (net (code "36") (name "OVCUR3") (class "Default")
      (node (ref "R2") (pin "2") (pinfunction "2_2") (pintype "passive"))
      (node (ref "U2") (pin "5") (pinfunction "*FLT_5") (pintype "passive"))
    )
    (net (code "37") (name "OVCUR4") (class "Default")
      (node (ref "R6") (pin "2") (pinfunction "2_2") (pintype "passive"))
      (node (ref "U4") (pin "5") (pinfunction "*FLT_5") (pintype "passive"))
    )
    (net (code "38") (name "P5V") (class "Default")
      (node (ref "C11") (pin "2") (pinfunction "2_2") (pintype "passive"))
      (node (ref "C12") (pin "2") (pinfunction "2_2") (pintype "passive"))
      (node (ref "C3") (pin "2") (pinfunction "2_2") (pintype "passive"))
      (node (ref "C4") (pin "2") (pinfunction "2_2") (pintype "passive"))
      (node (ref "U1") (pin "2") (pinfunction "IN_2") (pintype "input"))
      (node (ref "U1") (pin "3") (pinfunction "IN_3") (pintype "input"))
      (node (ref "U2") (pin "2") (pinfunction "IN_2") (pintype "input"))
      (node (ref "U2") (pin "3") (pinfunction "IN_3") (pintype "input"))
      (node (ref "U3") (pin "2") (pinfunction "IN_2") (pintype "input"))
      (node (ref "U3") (pin "3") (pinfunction "IN_3") (pintype "input"))
      (node (ref "U4") (pin "2") (pinfunction "IN_2") (pintype "input"))
      (node (ref "U4") (pin "3") (pinfunction "IN_3") (pintype "input"))
    )
    (net (code "39") (name "P5V_DP1") (class "Default")
      (node (ref "C10") (pin "2") (pinfunction "2_2") (pintype "passive"))
      (node (ref "C5") (pin "2") (pinfunction "2_2") (pintype "passive"))
      (node (ref "FB1") (pin "2") (pintype "passive"))
      (node (ref "R3") (pin "1") (pinfunction "1_1") (pintype "passive"))
      (node (ref "U1") (pin "6") (pinfunction "OUT_6") (pintype "output"))
      (node (ref "U1") (pin "7") (pinfunction "OUT_7") (pintype "output"))
      (node (ref "U1") (pin "8") (pinfunction "OUT_8") (pintype "output"))
    )
    (net (code "40") (name "P5V_DP2") (class "Default")
      (node (ref "C15") (pin "2") (pinfunction "2_2") (pintype "passive"))
      (node (ref "C20") (pin "2") (pinfunction "2_2") (pintype "passive"))
      (node (ref "FB2") (pin "2") (pintype "passive"))
      (node (ref "R7") (pin "1") (pinfunction "1_1") (pintype "passive"))
      (node (ref "U3") (pin "6") (pinfunction "OUT_6") (pintype "output"))
      (node (ref "U3") (pin "7") (pinfunction "OUT_7") (pintype "output"))
      (node (ref "U3") (pin "8") (pinfunction "OUT_8") (pintype "output"))
    )
    (net (code "41") (name "P5V_DP3") (class "Default")
      (node (ref "C28") (pin "2") (pinfunction "2_2") (pintype "passive"))
      (node (ref "C6") (pin "2") (pinfunction "2_2") (pintype "passive"))
      (node (ref "FB3") (pin "2") (pintype "passive"))
      (node (ref "R4") (pin "1") (pinfunction "1_1") (pintype "passive"))
      (node (ref "U2") (pin "6") (pinfunction "OUT_6") (pintype "output"))
      (node (ref "U2") (pin "7") (pinfunction "OUT_7") (pintype "output"))
      (node (ref "U2") (pin "8") (pinfunction "OUT_8") (pintype "output"))
    )
    (net (code "42") (name "P5V_DP4") (class "Default")
      (node (ref "C16") (pin "2") (pinfunction "2_2") (pintype "passive"))
      (node (ref "C36") (pin "2") (pinfunction "2_2") (pintype "passive"))
      (node (ref "FB5") (pin "2") (pintype "passive"))
      (node (ref "R8") (pin "1") (pinfunction "1_1") (pintype "passive"))
      (node (ref "U4") (pin "6") (pinfunction "OUT_6") (pintype "output"))
      (node (ref "U4") (pin "7") (pinfunction "OUT_7") (pintype "output"))
      (node (ref "U4") (pin "8") (pinfunction "OUT_8") (pintype "output"))
    )
    (net (code "43") (name "PWREN1") (class "Default")
      (node (ref "U1") (pin "4") (pinfunction "EN_4") (pintype "passive"))
    )
    (net (code "44") (name "PWREN2") (class "Default")
      (node (ref "U3") (pin "4") (pinfunction "EN_4") (pintype "passive"))
    )
    (net (code "45") (name "PWREN3") (class "Default")
      (node (ref "U2") (pin "4") (pinfunction "EN_4") (pintype "passive"))
    )
    (net (code "46") (name "PWREN4") (class "Default")
      (node (ref "U4") (pin "4") (pinfunction "EN_4") (pintype "passive"))
    )
    (net (code "47") (name "SHIELD") (class "Default")
      (node (ref "H1") (pin "1") (pintype "passive"))
      (node (ref "H2") (pin "1") (pintype "passive"))
      (node (ref "H3") (pin "1") (pintype "passive"))
      (node (ref "H4") (pin "1") (pintype "passive"))
      (node (ref "J1") (pin "G1") (pinfunction "G1_G1") (pintype "power_in"))
      (node (ref "J1") (pin "G2") (pinfunction "G2_G2") (pintype "power_in"))
      (node (ref "J2") (pin "G1") (pinfunction "G1_G1") (pintype "power_in"))
      (node (ref "J2") (pin "G2") (pinfunction "G2_G2") (pintype "power_in"))
      (node (ref "J3") (pin "G1") (pinfunction "G1_G1") (pintype "power_in"))
      (node (ref "J3") (pin "G2") (pinfunction "G2_G2") (pintype "power_in"))
      (node (ref "J4") (pin "G1") (pinfunction "G1_G1") (pintype "passive"))
      (node (ref "J4") (pin "G2") (pinfunction "G2_G2") (pintype "passive"))
      (node (ref "J4") (pin "G3") (pinfunction "G3_G3") (pintype "passive"))
      (node (ref "J4") (pin "G4") (pinfunction "G4_G4") (pintype "passive"))
      (node (ref "J4") (pin "G5") (pinfunction "G5_G5") (pintype "passive"))
      (node (ref "J4") (pin "G6") (pinfunction "G6_G6") (pintype "passive"))
      (node (ref "J5") (pin "G1") (pinfunction "G1_G1") (pintype "power_in"))
      (node (ref "J5") (pin "G2") (pinfunction "G2_G2") (pintype "power_in"))
    )
    (net (code "48") (name "SSRX0_N") (class "Default")
      (node (ref "D8") (pin "5") (pinfunction "K5_5") (pintype "passive"))
      (node (ref "D8") (pin "6") (pinfunction "K6_6") (pintype "passive"))
      (node (ref "J4") (pin "9") (pinfunction "SSRX+_9") (pintype "passive"))
    )
    (net (code "49") (name "SSRX0_P") (class "Default")
      (node (ref "D8") (pin "4") (pinfunction "K4_4") (pintype "passive"))
      (node (ref "D8") (pin "7") (pinfunction "K7_7") (pintype "passive"))
      (node (ref "J4") (pin "8") (pinfunction "SSRX-_8") (pintype "passive"))
    )
    (net (code "50") (name "SSRX1_N") (class "Default")
      (node (ref "D1") (pin "1") (pinfunction "K1_1") (pintype "passive"))
      (node (ref "D1") (pin "9") (pinfunction "K9_9") (pintype "passive"))
      (node (ref "J1") (pin "5") (pinfunction "SSRX-_5") (pintype "passive"))
    )
    (net (code "51") (name "SSRX1_P") (class "Default")
      (node (ref "D1") (pin "2") (pinfunction "K2_2") (pintype "passive"))
      (node (ref "D1") (pin "8") (pinfunction "K8_8") (pintype "passive"))
      (node (ref "J1") (pin "6") (pinfunction "SSRX+_6") (pintype "passive"))
    )
    (net (code "52") (name "SSRX2_N") (class "Default")
      (node (ref "D4") (pin "1") (pinfunction "K1_1") (pintype "passive"))
      (node (ref "D4") (pin "9") (pinfunction "K9_9") (pintype "passive"))
      (node (ref "J2") (pin "5") (pinfunction "SSRX-_5") (pintype "passive"))
    )
    (net (code "53") (name "SSRX2_P") (class "Default")
      (node (ref "D4") (pin "2") (pinfunction "K2_2") (pintype "passive"))
      (node (ref "D4") (pin "8") (pinfunction "K8_8") (pintype "passive"))
      (node (ref "J2") (pin "6") (pinfunction "SSRX+_6") (pintype "passive"))
    )
    (net (code "54") (name "SSRX3_N") (class "Default")
      (node (ref "D7") (pin "1") (pinfunction "K1_1") (pintype "passive"))
      (node (ref "D7") (pin "9") (pinfunction "K9_9") (pintype "passive"))
      (node (ref "J3") (pin "5") (pinfunction "SSRX-_5") (pintype "passive"))
    )
    (net (code "55") (name "SSRX3_P") (class "Default")
      (node (ref "D7") (pin "2") (pinfunction "K2_2") (pintype "passive"))
      (node (ref "D7") (pin "8") (pinfunction "K8_8") (pintype "passive"))
      (node (ref "J3") (pin "6") (pinfunction "SSRX+_6") (pintype "passive"))
    )
    (net (code "56") (name "SSRX4_N") (class "Default")
      (node (ref "D11") (pin "1") (pinfunction "K1_1") (pintype "passive"))
      (node (ref "D11") (pin "9") (pinfunction "K9_9") (pintype "passive"))
      (node (ref "J5") (pin "5") (pinfunction "SSRX-_5") (pintype "passive"))
    )
    (net (code "57") (name "SSRX4_P") (class "Default")
      (node (ref "D11") (pin "2") (pinfunction "K2_2") (pintype "passive"))
      (node (ref "D11") (pin "8") (pinfunction "K8_8") (pintype "passive"))
      (node (ref "J5") (pin "6") (pinfunction "SSRX+_6") (pintype "passive"))
    )
    (net (code "58") (name "SSTX0_N") (class "Default")
      (node (ref "C23") (pin "1") (pinfunction "1_1") (pintype "passive"))
    )
    (net (code "59") (name "SSTX0_P") (class "Default")
      (node (ref "C24") (pin "1") (pinfunction "1_1") (pintype "passive"))
    )
    (net (code "60") (name "SSTX1_N") (class "Default")
      (node (ref "C2") (pin "1") (pinfunction "1_1") (pintype "passive"))
    )
    (net (code "61") (name "SSTX1_P") (class "Default")
      (node (ref "C1") (pin "1") (pinfunction "1_1") (pintype "passive"))
    )
    (net (code "62") (name "SSTX2_N") (class "Default")
      (node (ref "C14") (pin "1") (pinfunction "1_1") (pintype "passive"))
    )
    (net (code "63") (name "SSTX2_P") (class "Default")
      (node (ref "C13") (pin "1") (pinfunction "1_1") (pintype "passive"))
    )
    (net (code "64") (name "SSTX3_N") (class "Default")
      (node (ref "C22") (pin "1") (pinfunction "1_1") (pintype "passive"))
    )
    (net (code "65") (name "SSTX3_P") (class "Default")
      (node (ref "C21") (pin "1") (pinfunction "1_1") (pintype "passive"))
    )
    (net (code "66") (name "SSTX4_N") (class "Default")
      (node (ref "C30") (pin "1") (pinfunction "1_1") (pintype "passive"))
    )
    (net (code "67") (name "SSTX4_P") (class "Default")
      (node (ref "C29") (pin "1") (pinfunction "1_1") (pintype "passive"))
    )
    (net (code "68") (name "USBDP_N") (class "Default")
      (node (ref "L4") (pin "3") (pinfunction "3_3") (pintype "passive"))
    )
    (net (code "69") (name "USBDP_P") (class "Default")
      (node (ref "L4") (pin "4") (pinfunction "4_4") (pintype "passive"))
    )
    (net (code "70") (name "USBHP1_N") (class "Default")
      (node (ref "L1") (pin "3") (pinfunction "3_3") (pintype "passive"))
    )
    (net (code "71") (name "USBHP1_P") (class "Default")
      (node (ref "L1") (pin "4") (pinfunction "4_4") (pintype "passive"))
    )
    (net (code "72") (name "USBHP2_N") (class "Default")
      (node (ref "L2") (pin "3") (pinfunction "3_3") (pintype "passive"))
    )
    (net (code "73") (name "USBHP2_P") (class "Default")
      (node (ref "L2") (pin "4") (pinfunction "4_4") (pintype "passive"))
    )
    (net (code "74") (name "USBHP3_N") (class "Default")
      (node (ref "L3") (pin "3") (pinfunction "3_3") (pintype "passive"))
    )
    (net (code "75") (name "USBHP3_P") (class "Default")
      (node (ref "L3") (pin "4") (pinfunction "4_4") (pintype "passive"))
    )
    (net (code "76") (name "USBHP4_N") (class "Default")
      (node (ref "L5") (pin "3") (pinfunction "3_3") (pintype "passive"))
    )
    (net (code "77") (name "USBHP4_P") (class "Default")
      (node (ref "L5") (pin "4") (pinfunction "4_4") (pintype "passive"))
    )
  )
)
